# VoltageScaling.net
KiCad netlist of a schematic drawn in Altium Designer
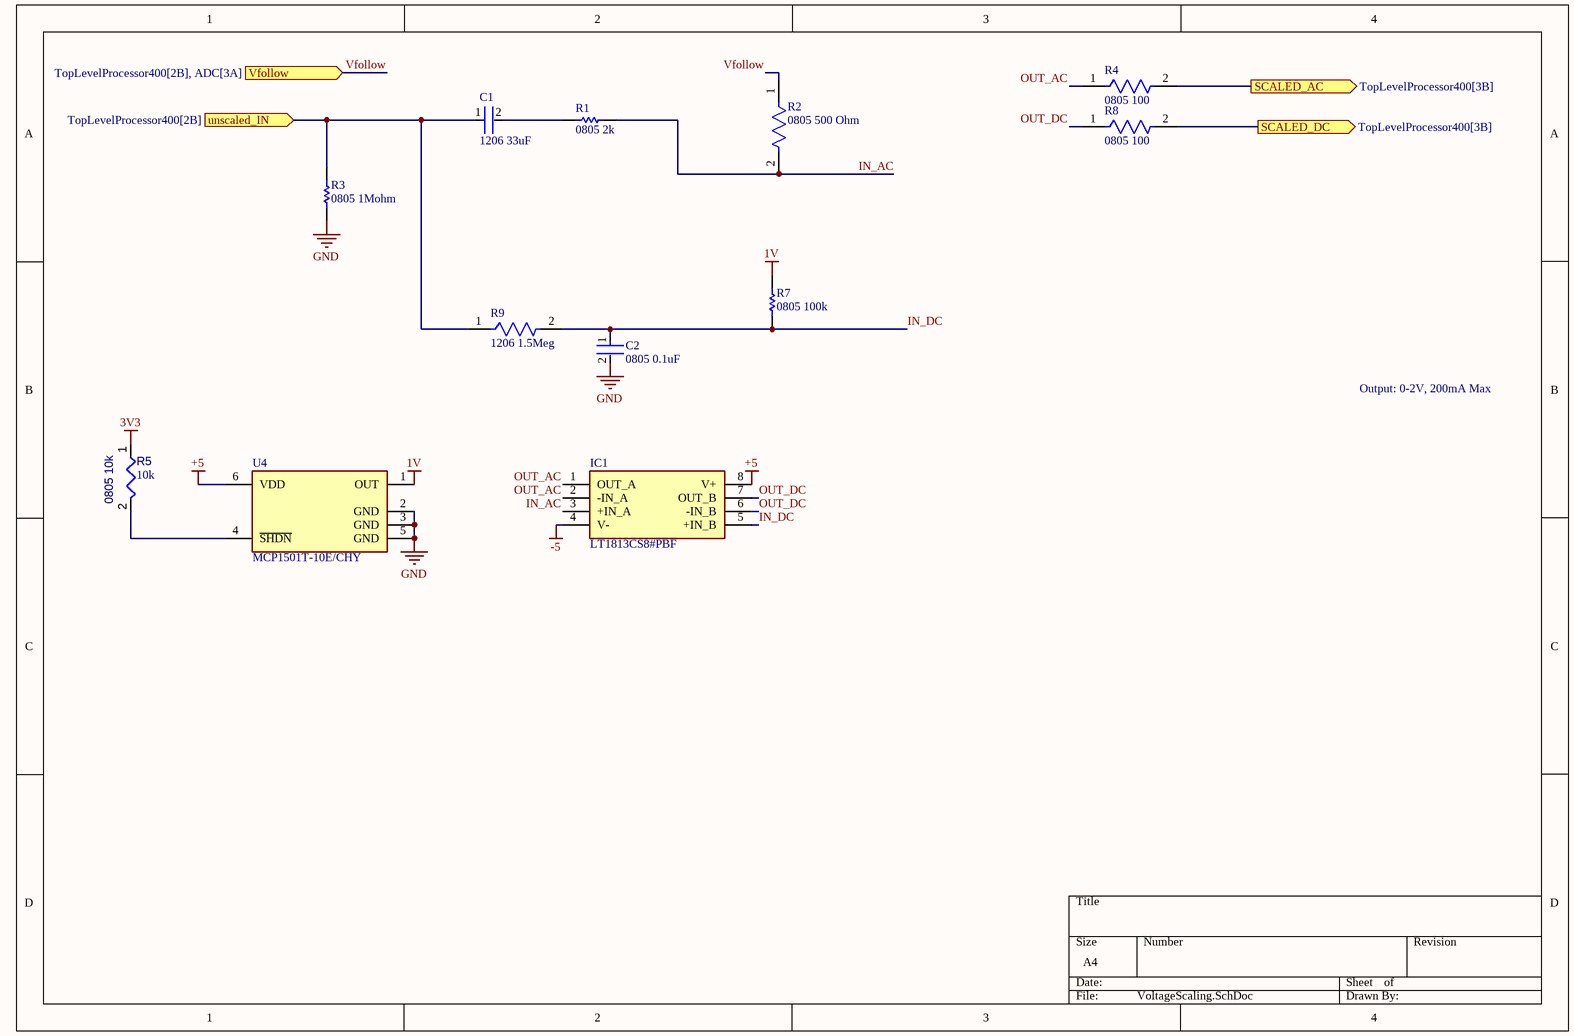
[diagram p0: VoltageScaling.SchDoc]

(export (version "E")
  (design (tool "Eeschema 10.0.6"))
  (components
    (comp (ref "C1")
      (value "1206 33uF")
      (footprint "FP-C3216-160-0_2-IPC_A")
      (description "Multilayer Ceramic Capacitors 33uF ±20% 25V X5R SMD 1206  C3216X5R1E336M160AC")
      (fields (field (name "TOLERANCE") "20%"))
      (libsource (lib "Altium Content Vault") (part "11868f565c42a9108669ba33697ecf6"))
    )
    (comp (ref "C2")
      (value "0805 0.1uF")
      (footprint "FP-0805B-IPC_C")
      (description "CAP CER 0.1UF 50V X7R 0805     0805B104K500CT")
      (fields (field (name "VOLTAGE") "50V") (field (name "TOLERANCE") "10%"))
      (libsource (lib "Altium Content Vault") (part "02cd4be3c70576c341d710602a673aa"))
    )
    (comp (ref "IC1")
      (value "LT1813CS8#PBF")
      (footprint "SamacSys:SOIC127P599X175-8N")
      (description "Integrated Circuit")
      (fields (field (name "MOUSER PART NUMBER") "584-LT1813CS8#PBF"))
      (libsource (lib "*") (part "LT1813CS8#PBF"))
    )
    (comp (ref "R1")
      (value "0805 2k")
      (footprint "RESC2013X60X30ML20T20")
      (description "RK73B2ATTD202J")
      (fields (field (name "MANUFACTURER") "KOA Speer"))
      (libsource (lib "Altium Content Vault") (part "RES"))
    )
    (comp (ref "R2")
      (value "0805 500 Ohm")
      (footprint "FP-RNCF0805-MFG")
      (fields (field (name "TOLERANCE") "0.01%"))
      (libsource (lib "Altium Content Vault") (part "1029c3af85768c4190bb7ad29bc67b5"))
    )
    (comp (ref "R3")
      (value "0805 1Mohm")
      (footprint "RESC2013X50X30LL20T20")
      (description "CRCW08051M00JNEA")
      (fields (field (name "MANUFACTURER") "Vishay Dale"))
      (libsource (lib "Altium Content Vault") (part "RES"))
    )
    (comp (ref "R4")
      (value "0805 100")
      (footprint "FP-TNPW0805-e3-MFG")
      (description "RES 100 OHM 0.1% 1/8W 0805    TNPW0805100RBYEN")
      (libsource (lib "Altium Content Vault") (part "1029c3af85768c4190bb7ad29bc67b5"))
    )
    (comp (ref "R5")
      (value "0805 10k")
      (footprint "RESC2013X50X35ML15T15")
      (description "Chip Resistor, 10 KOhm, +/- 1%, 125 mW, -55 to 155 degC, 0805 (2012 Metric)")
      (fields
        (field (name "TOLERANCE") "1%")
        (field (name "ALTIUM_VALUE") "10k")
        (field (name "POWER") "125mW")
      )
      (libsource (lib "Ibrahim Khalid") (part "RES-2"))
    )
    (comp (ref "R7")
      (value "0805 100k")
      (footprint "RESC2013X60X30LL20T20")
      (description "100k 0805    SG73S2ATTD1003F")
      (fields (field (name "PART NUMBER") "SG73S2ATTD1003F") (field (name "MANUFACTURER") "KOA Speer"))
      (libsource (lib "Altium Content Vault") (part "RES"))
    )
    (comp (ref "R8")
      (value "0805 100")
      (footprint "FP-TNPW0805-e3-MFG")
      (description "RES 100 OHM 0.1% 1/8W 0805    TNPW0805100RBYEN")
      (libsource (lib "Altium Content Vault") (part "1029c3af85768c4190bb7ad29bc67b5"))
    )
    (comp (ref "R9")
      (value "1206 1.5Meg")
      (footprint "FP-MCR18-MFG")
      (description "Thick Film Chip Resistor, 1206, 1.5MΩ, 5%, 200ppm/°C, 0.25W, 200V   MCR18FZHJ155")
      (fields (field (name "TOLERANCE") "5%"))
      (libsource (lib "Altium Content Vault") (part "1029c3af85768c4190bb7ad29bc67b5"))
    )
    (comp (ref "U4")
      (value "MCP1501T-10E/CHY")
      (footprint "FP-C04-028-IPC_C")
      (description "IC VREF SERIES 0.1% SOT23-6")
      (fields (field (name "TOLERANCE") "0.1%"))
      (libsource (lib "Altium Content Vault") (part "ad10a819a354f1b8528b4616d2402d9"))
    )
  )
  (nets
    (net (code "1") (name "+5") (class "Default")
      (node (ref "IC1") (pin "8") (pinfunction "V+_8") (pintype "passive"))
      (node (ref "U4") (pin "6") (pinfunction "VDD_6") (pintype "power_in"))
    )
    (net (code "2") (name "-5") (class "Default")
      (node (ref "IC1") (pin "4") (pinfunction "V-_4") (pintype "passive"))
    )
    (net (code "3") (name "/IN_AC") (class "Default")
      (node (ref "IC1") (pin "3") (pinfunction "+IN_A_3") (pintype "passive"))
      (node (ref "R1") (pin "2") (pinfunction "2_2") (pintype "passive"))
      (node (ref "R2") (pin "2") (pinfunction "2_2") (pintype "passive"))
    )
    (net (code "4") (name "/IN_DC") (class "Default")
      (node (ref "C2") (pin "1") (pinfunction "1_1") (pintype "passive"))
      (node (ref "IC1") (pin "5") (pinfunction "+IN_B_5") (pintype "passive"))
      (node (ref "R7") (pin "2") (pinfunction "2_2") (pintype "passive"))
      (node (ref "R9") (pin "2") (pinfunction "2_2") (pintype "passive"))
    )
    (net (code "5") (name "/OUT_AC") (class "Default")
      (node (ref "IC1") (pin "1") (pinfunction "OUT_A_1") (pintype "passive"))
      (node (ref "IC1") (pin "2") (pinfunction "-IN_A_2") (pintype "passive"))
      (node (ref "R4") (pin "1") (pinfunction "1_1") (pintype "passive"))
    )
    (net (code "6") (name "/OUT_DC") (class "Default")
      (node (ref "IC1") (pin "6") (pinfunction "-IN_B_6") (pintype "passive"))
      (node (ref "IC1") (pin "7") (pinfunction "OUT_B_7") (pintype "passive"))
      (node (ref "R8") (pin "1") (pinfunction "1_1") (pintype "passive"))
    )
    (net (code "7") (name "/SCALED_AC") (class "Default")
      (node (ref "R4") (pin "2") (pinfunction "2_2") (pintype "passive"))
    )
    (net (code "8") (name "/SCALED_DC") (class "Default")
      (node (ref "R8") (pin "2") (pinfunction "2_2") (pintype "passive"))
    )
    (net (code "9") (name "/Vfollow") (class "Default")
      (node (ref "R2") (pin "1") (pinfunction "1_1") (pintype "passive"))
    )
    (net (code "10") (name "/unscaled_IN") (class "Default")
      (node (ref "C1") (pin "1") (pinfunction "1_1") (pintype "passive"))
      (node (ref "R3") (pin "1") (pinfunction "1_1") (pintype "passive"))
      (node (ref "R9") (pin "1") (pinfunction "1_1") (pintype "passive"))
    )
    (net (code "11") (name "1V") (class "Default")
      (node (ref "R7") (pin "1") (pinfunction "1_1") (pintype "passive"))
      (node (ref "U4") (pin "1") (pinfunction "OUT_1") (pintype "power_in"))
    )
    (net (code "12") (name "3V3") (class "Default")
      (node (ref "R5") (pin "1") (pinfunction "1_1") (pintype "passive"))
    )
    (net (code "13") (name "GND") (class "Default")
      (node (ref "C2") (pin "2") (pinfunction "2_2") (pintype "passive"))
      (node (ref "R3") (pin "2") (pinfunction "2_2") (pintype "passive"))
      (node (ref "U4") (pin "2") (pinfunction "GND_2") (pintype "power_in"))
      (node (ref "U4") (pin "3") (pinfunction "GND_3") (pintype "power_in"))
      (node (ref "U4") (pin "5") (pinfunction "GND_5") (pintype "power_in"))
    )
    (net (code "14") (name "Net-(C1-Pad2)") (class "Default")
      (node (ref "C1") (pin "2") (pinfunction "2_2") (pintype "passive"))
      (node (ref "R1") (pin "1") (pinfunction "1_1") (pintype "passive"))
    )
    (net (code "15") (name "Net-(U4-~{SHDN})") (class "Default")
      (node (ref "R5") (pin "2") (pinfunction "2_2") (pintype "passive"))
      (node (ref "U4") (pin "4") (pinfunction "~{SHDN}_4") (pintype "passive"))
    )
  )
)
